# Sheet1.net
KiCad netlist of a schematic drawn in Altium Designer
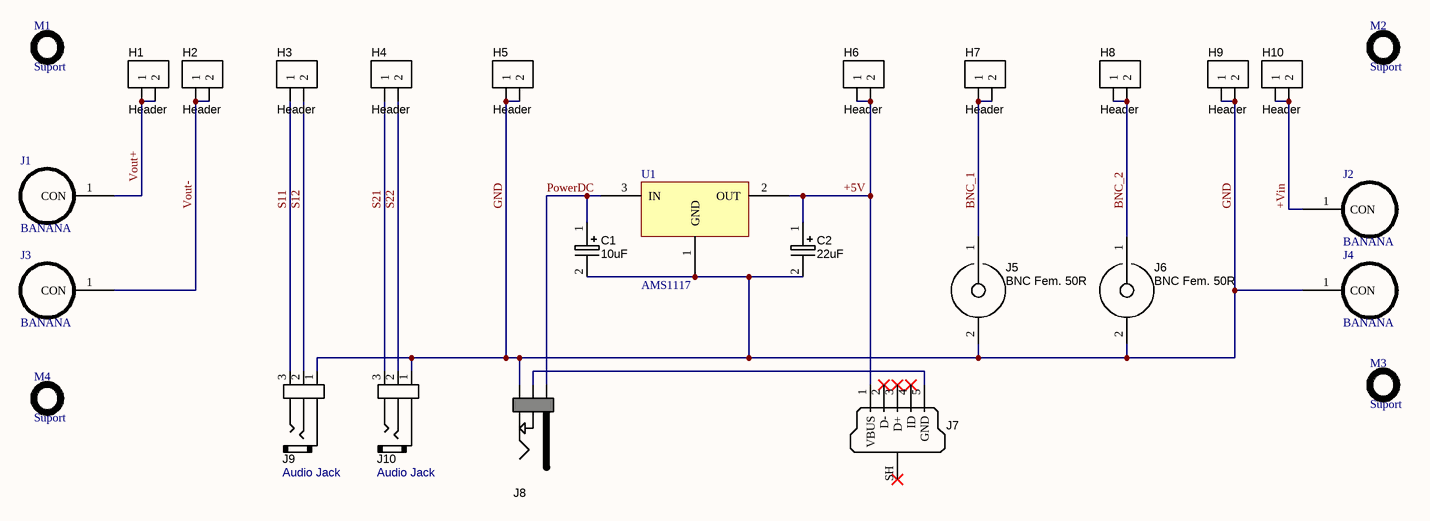
[diagram p0: Sheet1.SchDoc]

(export (version "E")
  (design (tool "Eeschema 10.0.6"))
  (components
    (comp (ref "C1") (value "10uF") (footprint "Capacitor_E") (libsource (lib "Schlib1") (part "CAPE")))
    (comp (ref "C2") (value "22uF") (footprint "Capacitor_E") (libsource (lib "Schlib1") (part "CAPE")))
    (comp (ref "H1")
      (value "Header")
      (footprint "HDR1X2")
      (description "Header, 2-pin")
      (libsource (lib "Schlib1") (part "Header2P"))
    )
    (comp (ref "H2")
      (value "Header")
      (footprint "HDR1X2")
      (description "Header, 2-pin")
      (libsource (lib "Schlib1") (part "Header2P"))
    )
    (comp (ref "H3")
      (value "Header")
      (footprint "HDR1X2")
      (description "Header, 2-pin")
      (libsource (lib "Schlib1") (part "Header2P"))
    )
    (comp (ref "H4")
      (value "Header")
      (footprint "HDR1X2")
      (description "Header, 2-pin")
      (libsource (lib "Schlib1") (part "Header2P"))
    )
    (comp (ref "H5")
      (value "Header")
      (footprint "HDR1X2")
      (description "Header, 2-pin")
      (libsource (lib "Schlib1") (part "Header2P"))
    )
    (comp (ref "H6")
      (value "Header")
      (footprint "HDR1X2")
      (description "Header, 2-pin")
      (libsource (lib "Schlib1") (part "Header2P"))
    )
    (comp (ref "H7")
      (value "Header")
      (footprint "HDR1X2")
      (description "Header, 2-pin")
      (libsource (lib "Schlib1") (part "Header2P"))
    )
    (comp (ref "H8")
      (value "Header")
      (footprint "HDR1X2")
      (description "Header, 2-pin")
      (libsource (lib "Schlib1") (part "Header2P"))
    )
    (comp (ref "H9")
      (value "Header")
      (footprint "HDR1X2")
      (description "Header, 2-pin")
      (libsource (lib "Schlib1") (part "Header2P"))
    )
    (comp (ref "H10")
      (value "Header")
      (footprint "HDR1X2")
      (description "Header, 2-pin")
      (libsource (lib "Schlib1") (part "Header2P"))
    )
    (comp (ref "J1")
      (value "BANANA")
      (footprint "Banana")
      (description "Female Connector")
      (libsource (lib "Schlib1") (part "BANANA"))
    )
    (comp (ref "J2")
      (value "BANANA")
      (footprint "Banana")
      (description "Female Connector")
      (libsource (lib "Schlib1") (part "BANANA"))
    )
    (comp (ref "J3")
      (value "BANANA")
      (footprint "Banana")
      (description "Female Connector")
      (libsource (lib "Schlib1") (part "BANANA"))
    )
    (comp (ref "J4")
      (value "BANANA")
      (footprint "Banana")
      (description "Female Connector")
      (libsource (lib "Schlib1") (part "BANANA"))
    )
    (comp (ref "J5")
      (value "BNC Fem. 50R")
      (footprint "CONN_BNC")
      (description "Connector BNC 50 Ohm right-angle PCB mounted")
      (libsource (lib "Schlib1") (part "CONN_BNC_FEM_50R"))
    )
    (comp (ref "J6")
      (value "BNC Fem. 50R")
      (footprint "CONN_BNC")
      (description "Connector BNC 50 Ohm right-angle PCB mounted")
      (libsource (lib "Schlib1") (part "CONN_BNC_FEM_50R"))
    )
    (comp (ref "J7")
      (value "USB Micro Type B (recommended if hand soldering)")
      (footprint "USB_MICRO-B_v2")
      (description "Connector SMD-THD USB Micro Type B middle mount")
      (libsource (lib "Schlib1") (part "USB_Micro_TypeB_FCI"))
    )
    (comp (ref "J8")
      (value "CONN_PWR_JACK_2.1x5.5mm")
      (footprint "CONN_PWR_JACK_2.1x5.5mm")
      (libsource (lib "Schlib1") (part "CONN_PWR_JACK_2.1x5.5mm"))
    )
    (comp (ref "J9")
      (value "Audio Jack")
      (footprint "CONN_AUDIO")
      (description "Stereo phone jack mini")
      (libsource (lib "Schlib1") (part "CONN_MINIPHONEJACK"))
    )
    (comp (ref "J10")
      (value "Audio Jack")
      (footprint "CONN_AUDIO")
      (description "Stereo phone jack mini")
      (libsource (lib "Schlib1") (part "CONN_MINIPHONEJACK"))
    )
    (comp (ref "M1") (value "Suport") (footprint "Support") (libsource (lib "Schlib1") (part "Suport")))
    (comp (ref "M2") (value "Suport") (footprint "Support") (libsource (lib "Schlib1") (part "Suport")))
    (comp (ref "M3") (value "Suport") (footprint "Support") (libsource (lib "Schlib1") (part "Suport")))
    (comp (ref "M4") (value "Suport") (footprint "Support") (libsource (lib "Schlib1") (part "Suport")))
    (comp (ref "U1")
      (value "AMS1117")
      (footprint "SOT223")
      (description "Voltage Regulator")
      (libsource (lib "Schlib1") (part "AMS1117"))
    )
  )
  (nets
    (net (code "1") (name "/+5V") (class "Default")
      (node (ref "C2") (pin "1") (pinfunction "1_1") (pintype "passive"))
      (node (ref "H6") (pin "1") (pinfunction "1_1") (pintype "passive"))
      (node (ref "H6") (pin "2") (pinfunction "2_2") (pintype "passive"))
      (node (ref "J7") (pin "1") (pinfunction "VBUS_1") (pintype "passive"))
      (node (ref "U1") (pin "2") (pinfunction "OUT_2") (pintype "passive"))
    )
    (net (code "2") (name "/+Vin") (class "Default")
      (node (ref "H10") (pin "1") (pinfunction "1_1") (pintype "passive"))
      (node (ref "H10") (pin "2") (pinfunction "2_2") (pintype "passive"))
      (node (ref "J2") (pin "1") (pinfunction "CON_1") (pintype "passive"))
    )
    (net (code "3") (name "/BNC_1") (class "Default")
      (node (ref "H7") (pin "1") (pinfunction "1_1") (pintype "passive"))
      (node (ref "H7") (pin "2") (pinfunction "2_2") (pintype "passive"))
      (node (ref "J5") (pin "1") (pinfunction "1_1") (pintype "passive"))
    )
    (net (code "4") (name "/BNC_2") (class "Default")
      (node (ref "H8") (pin "1") (pinfunction "1_1") (pintype "passive"))
      (node (ref "H8") (pin "2") (pinfunction "2_2") (pintype "passive"))
      (node (ref "J6") (pin "1") (pinfunction "1_1") (pintype "passive"))
    )
    (net (code "5") (name "/GND") (class "Default")
      (node (ref "C1") (pin "2") (pinfunction "2_2") (pintype "passive"))
      (node (ref "C2") (pin "2") (pinfunction "2_2") (pintype "passive"))
      (node (ref "H5") (pin "1") (pinfunction "1_1") (pintype "passive"))
      (node (ref "H5") (pin "2") (pinfunction "2_2") (pintype "passive"))
      (node (ref "H9") (pin "1") (pinfunction "1_1") (pintype "passive"))
      (node (ref "H9") (pin "2") (pinfunction "2_2") (pintype "passive"))
      (node (ref "J10") (pin "1") (pinfunction "Base_1") (pintype "passive"))
      (node (ref "J4") (pin "1") (pinfunction "CON_1") (pintype "passive"))
      (node (ref "J5") (pin "2") (pinfunction "2_2") (pintype "passive"))
      (node (ref "J6") (pin "2") (pinfunction "2_2") (pintype "passive"))
      (node (ref "J8") (pin "2") (pinfunction "2_2") (pintype "passive"))
      (node (ref "J9") (pin "1") (pinfunction "Base_1") (pintype "passive"))
      (node (ref "U1") (pin "1") (pinfunction "GND_1") (pintype "passive"))
    )
    (net (code "6") (name "/PowerDC") (class "Default")
      (node (ref "C1") (pin "1") (pinfunction "1_1") (pintype "passive"))
      (node (ref "J8") (pin "1") (pinfunction "1_1") (pintype "passive"))
      (node (ref "U1") (pin "3") (pinfunction "IN_3") (pintype "passive"))
    )
    (net (code "7") (name "/S11") (class "Default")
      (node (ref "H3") (pin "1") (pinfunction "1_1") (pintype "passive"))
      (node (ref "J9") (pin "3") (pinfunction "TIP_3") (pintype "passive"))
    )
    (net (code "8") (name "/S12") (class "Default")
      (node (ref "H3") (pin "2") (pinfunction "2_2") (pintype "passive"))
      (node (ref "J9") (pin "2") (pinfunction "Middle_2") (pintype "passive"))
    )
    (net (code "9") (name "/S21") (class "Default")
      (node (ref "H4") (pin "1") (pinfunction "1_1") (pintype "passive"))
      (node (ref "J10") (pin "3") (pinfunction "TIP_3") (pintype "passive"))
    )
    (net (code "10") (name "/S22") (class "Default")
      (node (ref "H4") (pin "2") (pinfunction "2_2") (pintype "passive"))
      (node (ref "J10") (pin "2") (pinfunction "Middle_2") (pintype "passive"))
    )
    (net (code "11") (name "/Vout+") (class "Default")
      (node (ref "H1") (pin "1") (pinfunction "1_1") (pintype "passive"))
      (node (ref "H1") (pin "2") (pinfunction "2_2") (pintype "passive"))
      (node (ref "J1") (pin "1") (pinfunction "CON_1") (pintype "passive"))
    )
    (net (code "12") (name "/Vout-") (class "Default")
      (node (ref "H2") (pin "1") (pinfunction "1_1") (pintype "passive"))
      (node (ref "H2") (pin "2") (pinfunction "2_2") (pintype "passive"))
      (node (ref "J3") (pin "1") (pinfunction "CON_1") (pintype "passive"))
    )
    (net (code "13") (name "Net-(J7-GND)") (class "Default")
      (node (ref "J7") (pin "5") (pinfunction "GND_5") (pintype "passive"))
      (node (ref "J8") (pin "3") (pinfunction "3_3") (pintype "passive"))
    )
    (net (code "14") (name "unconnected-(J7-D+-Pad3)") (class "Default")
      (node (ref "J7") (pin "3") (pinfunction "D+_3") (pintype "passive+no_connect"))
    )
    (net (code "15") (name "unconnected-(J7-D--Pad2)") (class "Default")
      (node (ref "J7") (pin "2") (pinfunction "D-_2") (pintype "passive+no_connect"))
    )
    (net (code "16") (name "unconnected-(J7-ID-Pad4)") (class "Default")
      (node (ref "J7") (pin "4") (pinfunction "ID_4") (pintype "passive+no_connect"))
    )
    (net (code "17") (name "unconnected-(J7-Shell-PadSH)") (class "Default")
      (node (ref "J7") (pin "SH") (pinfunction "Shell_SH") (pintype "passive+no_connect"))
    )
  )
)
